# receiver.net
KiCad netlist of a schematic drawn in EAGLE
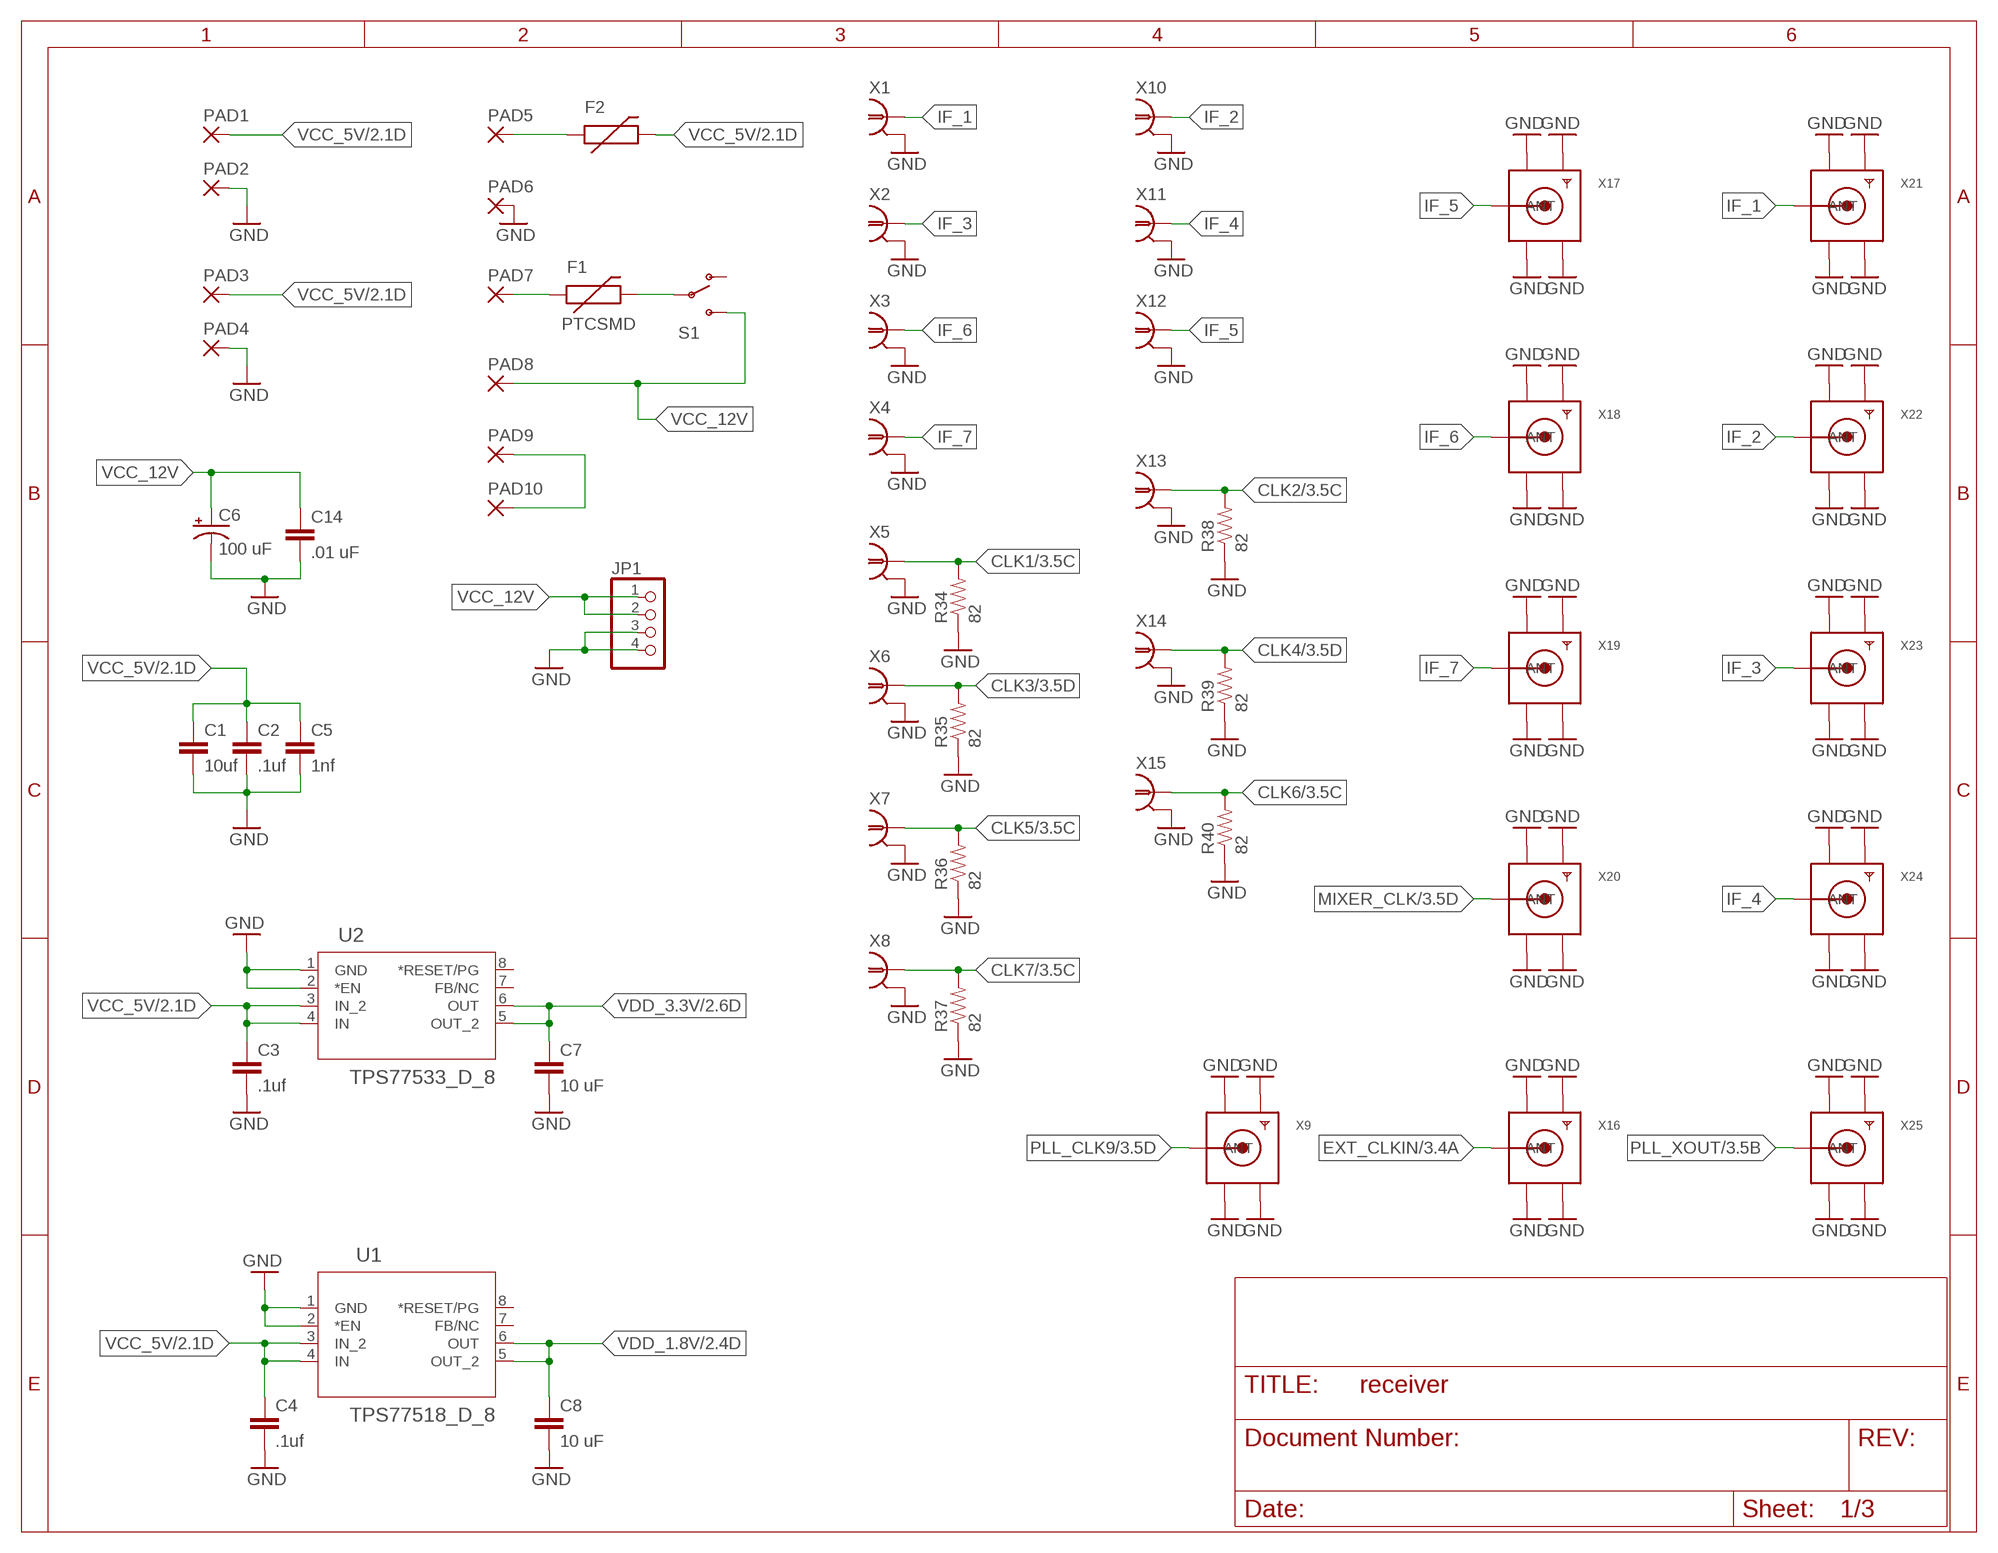
[diagram p0: schematic, sheet 1]
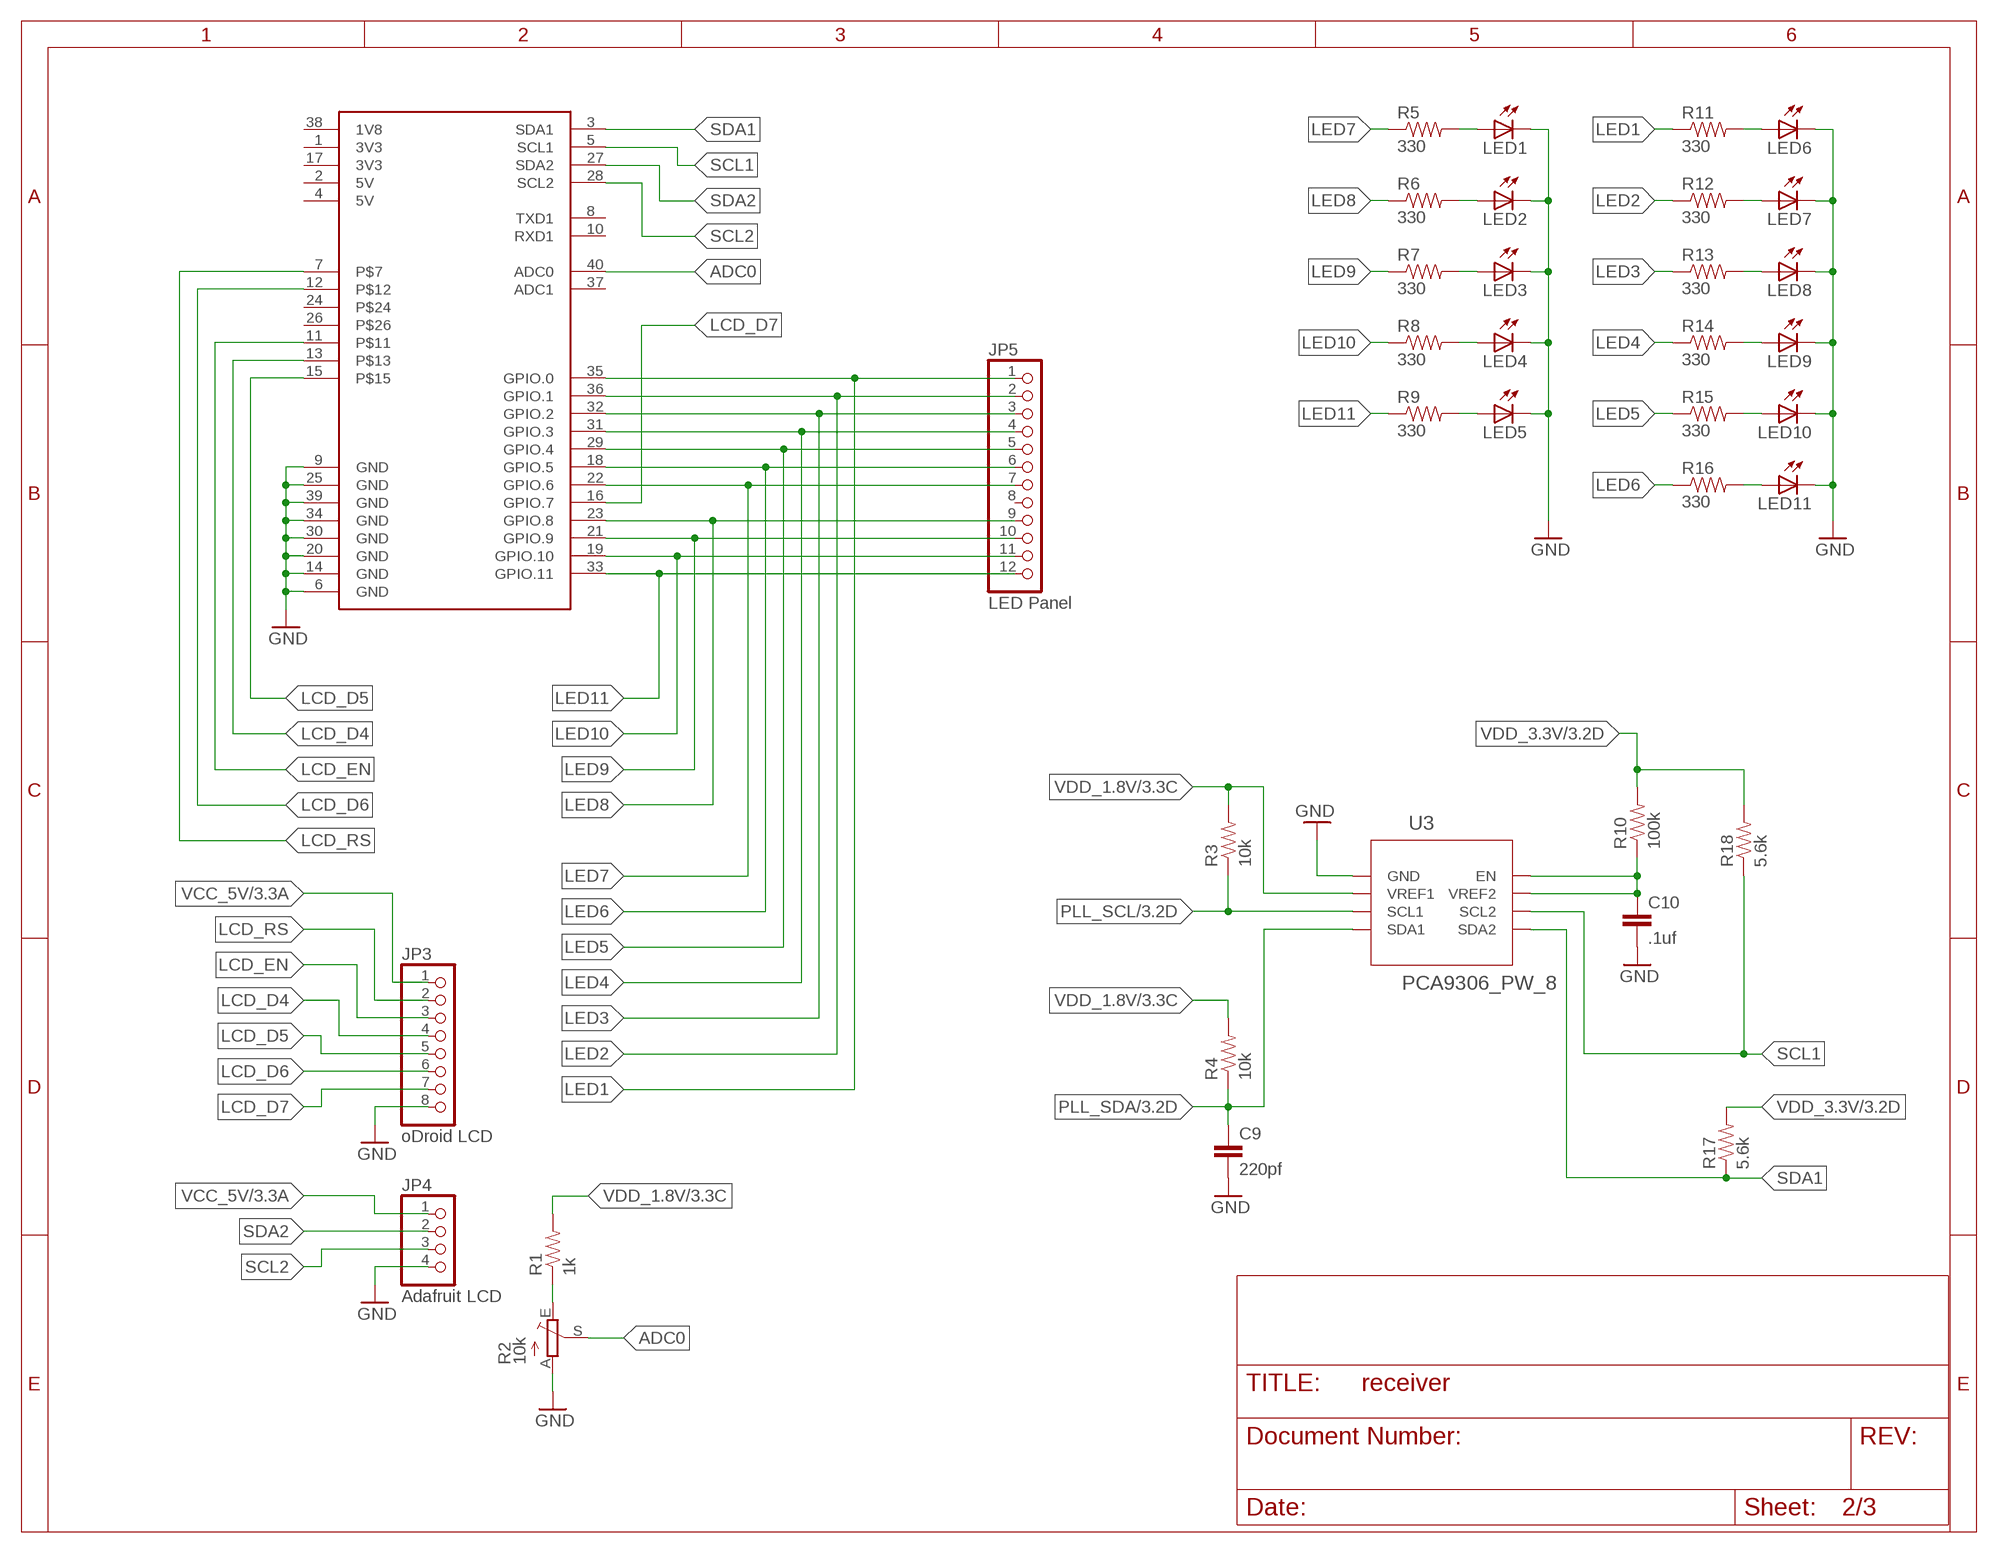
[diagram p1: schematic, sheet 2]
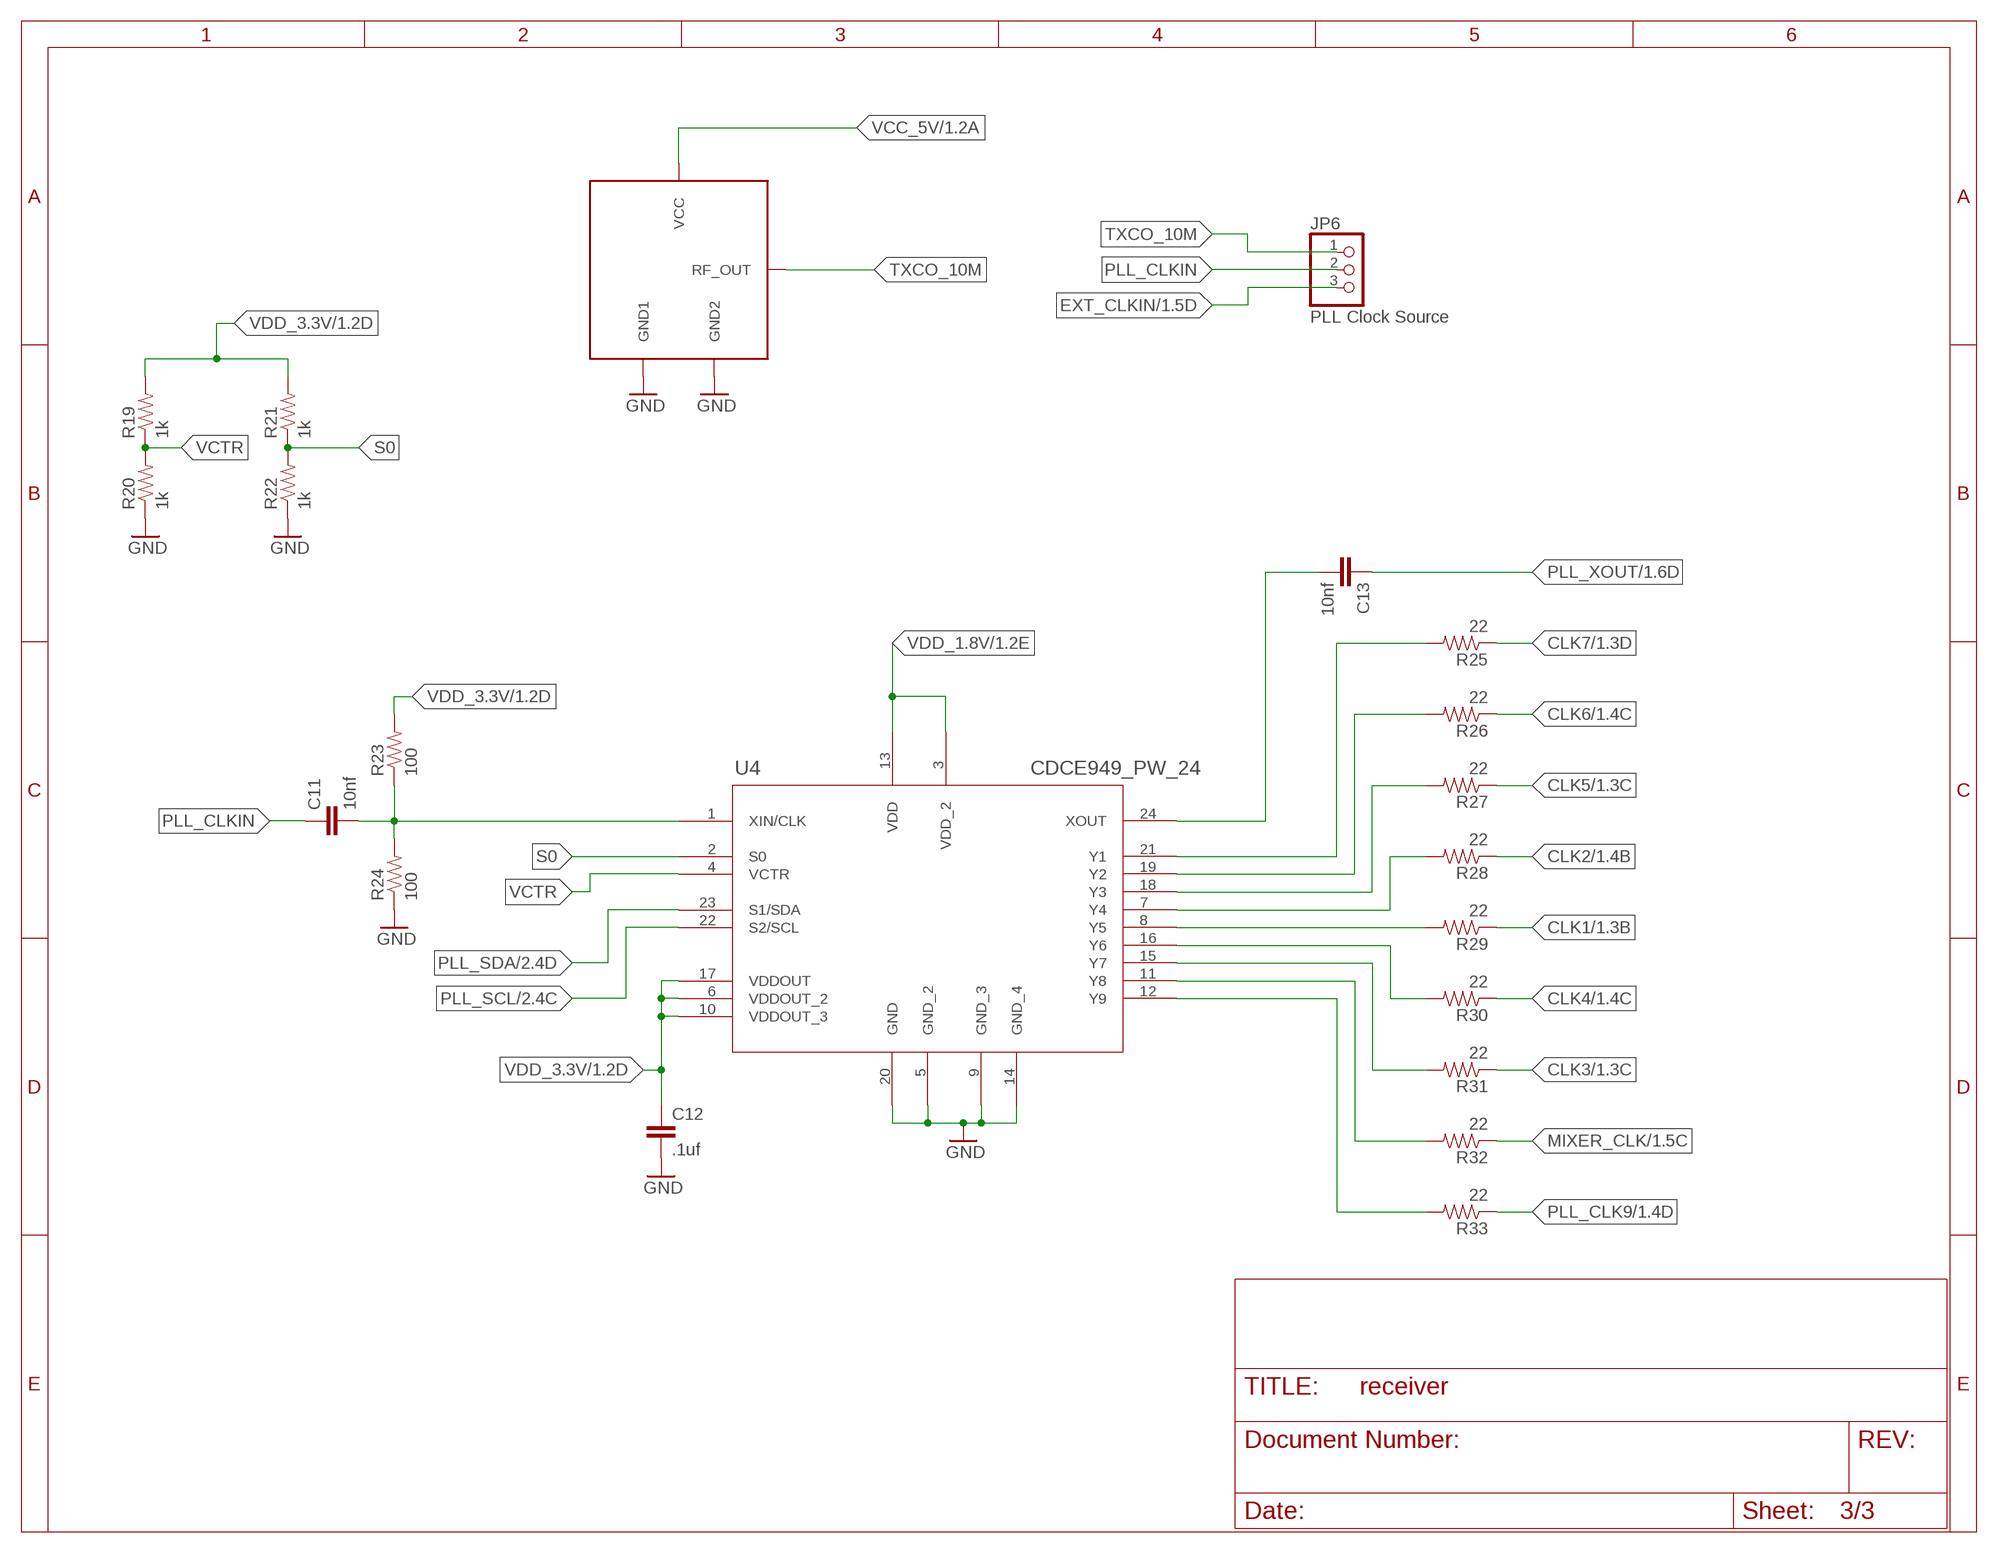
[diagram p2: schematic, sheet 3]

(export (version "E")
  (design (tool "Eeschema 10.0.6"))
  (components
    (comp (ref "C1")
      (value "10uf")
      (footprint "eagle-import:1206")
      (libsource (lib "eagle-import") (part "CAP1206"))
    )
    (comp (ref "C2")
      (value ".1uf")
      (footprint "eagle-import:0805")
      (libsource (lib "eagle-import") (part "CAP0805"))
    )
    (comp (ref "C3")
      (value ".1uf")
      (footprint "eagle-import:0805")
      (libsource (lib "eagle-import") (part "CAP0805"))
    )
    (comp (ref "C4")
      (value ".1uf")
      (footprint "eagle-import:0805")
      (libsource (lib "eagle-import") (part "CAP0805"))
    )
    (comp (ref "C5")
      (value "1nf")
      (footprint "eagle-import:0805")
      (libsource (lib "eagle-import") (part "CAP0805"))
    )
    (comp (ref "C6")
      (value "100 uF")
      (footprint "eagle-import:CPOL-RADIAL-1000UF-25V")
      (libsource (lib "eagle-import") (part "CAP_POLPTH4"))
    )
    (comp (ref "C7")
      (value "10 uF")
      (footprint "eagle-import:1206")
      (libsource (lib "eagle-import") (part "CAP1206"))
    )
    (comp (ref "C8")
      (value "10 uF")
      (footprint "eagle-import:1206")
      (libsource (lib "eagle-import") (part "CAP1206"))
    )
    (comp (ref "C14")
      (value ".01 uF")
      (footprint "eagle-import:0805")
      (libsource (lib "eagle-import") (part "CAP0805"))
    )
    (comp (ref "F1")
      (value "PTCSMD")
      (footprint "eagle-import:PTC-1206")
      (libsource (lib "eagle-import") (part "PTCSMD"))
    )
    (comp (ref "F2")
      (value "PTCSMD")
      (footprint "eagle-import:PTC-1206")
      (libsource (lib "eagle-import") (part "PTCSMD"))
    )
    (comp (ref "JP1")
      (value "PINHD-1X4")
      (footprint "eagle-import:1X04")
      (libsource (lib "eagle-import") (part "PINHD-1X4"))
    )
    (comp (ref "PAD1")
      (value "WIREPAD2,54/0,9")
      (footprint "eagle-import:2,54_0,9")
      (libsource (lib "eagle-import") (part "WIREPAD2,54/0,9"))
    )
    (comp (ref "PAD2")
      (value "WIREPAD2,54/0,9")
      (footprint "eagle-import:2,54_0,9")
      (libsource (lib "eagle-import") (part "WIREPAD2,54/0,9"))
    )
    (comp (ref "PAD3")
      (value "WIREPAD2,54/0,9")
      (footprint "eagle-import:2,54_0,9")
      (libsource (lib "eagle-import") (part "WIREPAD2,54/0,9"))
    )
    (comp (ref "PAD4")
      (value "WIREPAD2,54/0,9")
      (footprint "eagle-import:2,54_0,9")
      (libsource (lib "eagle-import") (part "WIREPAD2,54/0,9"))
    )
    (comp (ref "PAD5")
      (value "WIREPAD2,54/0,9")
      (footprint "eagle-import:2,54_0,9")
      (libsource (lib "eagle-import") (part "WIREPAD2,54/0,9"))
    )
    (comp (ref "PAD6")
      (value "WIREPAD2,54/0,9")
      (footprint "eagle-import:2,54_0,9")
      (libsource (lib "eagle-import") (part "WIREPAD2,54/0,9"))
    )
    (comp (ref "PAD7")
      (value "WIREPAD2,54/0,9")
      (footprint "eagle-import:2,54_0,9")
      (libsource (lib "eagle-import") (part "WIREPAD2,54/0,9"))
    )
    (comp (ref "PAD8")
      (value "WIREPAD2,54/0,9")
      (footprint "eagle-import:2,54_0,9")
      (libsource (lib "eagle-import") (part "WIREPAD2,54/0,9"))
    )
    (comp (ref "PAD9")
      (value "WIREPAD2,54/0,9")
      (footprint "eagle-import:2,54_0,9")
      (libsource (lib "eagle-import") (part "WIREPAD2,54/0,9"))
    )
    (comp (ref "PAD10")
      (value "WIREPAD2,54/0,9")
      (footprint "eagle-import:2,54_0,9")
      (libsource (lib "eagle-import") (part "WIREPAD2,54/0,9"))
    )
    (comp (ref "R34")
      (value "82")
      (footprint "eagle-import:0805")
      (libsource (lib "eagle-import") (part "RESISTOR0805-RES"))
    )
    (comp (ref "R35")
      (value "82")
      (footprint "eagle-import:0805")
      (libsource (lib "eagle-import") (part "RESISTOR0805-RES"))
    )
    (comp (ref "R36")
      (value "82")
      (footprint "eagle-import:0805")
      (libsource (lib "eagle-import") (part "RESISTOR0805-RES"))
    )
    (comp (ref "R37")
      (value "82")
      (footprint "eagle-import:0805")
      (libsource (lib "eagle-import") (part "RESISTOR0805-RES"))
    )
    (comp (ref "R38")
      (value "82")
      (footprint "eagle-import:0805")
      (libsource (lib "eagle-import") (part "RESISTOR0805-RES"))
    )
    (comp (ref "R39")
      (value "82")
      (footprint "eagle-import:0805")
      (libsource (lib "eagle-import") (part "RESISTOR0805-RES"))
    )
    (comp (ref "R40")
      (value "82")
      (footprint "eagle-import:0805")
      (libsource (lib "eagle-import") (part "RESISTOR0805-RES"))
    )
    (comp (ref "S1")
      (value "SWITCH-SPDTPTH")
      (footprint "eagle-import:SWITCH-SPDT")
      (libsource (lib "eagle-import") (part "SWITCH-SPDTPTH"))
    )
    (comp (ref "U1")
      (value "TPS77518_D_8")
      (footprint "eagle-import:D8")
      (fields
        (field (name "GENERIC_PART_NUMBER") "TPS77518")
        (field (name "MANUFACTURER") "Texas Instruments")
        (field (name "MANUFACTURER_PART_NUMBER") "tps77518_d_8")
      )
      (libsource (lib "eagle-import") (part "TPS77518_D_8"))
    )
    (comp (ref "U2")
      (value "TPS77533_D_8")
      (footprint "eagle-import:D8")
      (fields
        (field (name "GENERIC_PART_NUMBER") "TPS77533")
        (field (name "MANUFACTURER") "Texas Instruments")
        (field (name "MANUFACTURER_PART_NUMBER") "tps77533_d_8")
      )
      (libsource (lib "eagle-import") (part "TPS77533_D_8"))
    )
    (comp (ref "X1")
      (value "LTI-SASF54GT")
      (footprint "eagle-import:LTI-SASF54GT")
      (libsource (lib "eagle-import") (part "LTI-SASF54GT"))
    )
    (comp (ref "X2")
      (value "LTI-SASF54GT")
      (footprint "eagle-import:LTI-SASF54GT")
      (libsource (lib "eagle-import") (part "LTI-SASF54GT"))
    )
    (comp (ref "X3")
      (value "LTI-SASF54GT")
      (footprint "eagle-import:LTI-SASF54GT")
      (libsource (lib "eagle-import") (part "LTI-SASF54GT"))
    )
    (comp (ref "X4")
      (value "LTI-SASF54GT")
      (footprint "eagle-import:LTI-SASF54GT")
      (libsource (lib "eagle-import") (part "LTI-SASF54GT"))
    )
    (comp (ref "X5")
      (value "LTI-SASF54GT")
      (footprint "eagle-import:LTI-SASF54GT")
      (libsource (lib "eagle-import") (part "LTI-SASF54GT"))
    )
    (comp (ref "X6")
      (value "LTI-SASF54GT")
      (footprint "eagle-import:LTI-SASF54GT")
      (libsource (lib "eagle-import") (part "LTI-SASF54GT"))
    )
    (comp (ref "X7")
      (value "LTI-SASF54GT")
      (footprint "eagle-import:LTI-SASF54GT")
      (libsource (lib "eagle-import") (part "LTI-SASF54GT"))
    )
    (comp (ref "X8")
      (value "LTI-SASF54GT")
      (footprint "eagle-import:LTI-SASF54GT")
      (libsource (lib "eagle-import") (part "LTI-SASF54GT"))
    )
    (comp (ref "X9")
      (value "SMACONNECTOR_EDGE")
      (footprint "eagle-import:SMA_EDGELAUNCH")
      (libsource (lib "eagle-import") (part "SMACONNECTOR_EDGE"))
    )
    (comp (ref "X10")
      (value "LTI-SASF54GT")
      (footprint "eagle-import:LTI-SASF54GT")
      (libsource (lib "eagle-import") (part "LTI-SASF54GT"))
    )
    (comp (ref "X11")
      (value "LTI-SASF54GT")
      (footprint "eagle-import:LTI-SASF54GT")
      (libsource (lib "eagle-import") (part "LTI-SASF54GT"))
    )
    (comp (ref "X12")
      (value "LTI-SASF54GT")
      (footprint "eagle-import:LTI-SASF54GT")
      (libsource (lib "eagle-import") (part "LTI-SASF54GT"))
    )
    (comp (ref "X13")
      (value "LTI-SASF54GT")
      (footprint "eagle-import:LTI-SASF54GT")
      (libsource (lib "eagle-import") (part "LTI-SASF54GT"))
    )
    (comp (ref "X14")
      (value "LTI-SASF54GT")
      (footprint "eagle-import:LTI-SASF54GT")
      (libsource (lib "eagle-import") (part "LTI-SASF54GT"))
    )
    (comp (ref "X15")
      (value "LTI-SASF54GT")
      (footprint "eagle-import:LTI-SASF54GT")
      (libsource (lib "eagle-import") (part "LTI-SASF54GT"))
    )
    (comp (ref "X16")
      (value "SMACONNECTOR_EDGE")
      (footprint "eagle-import:SMA_EDGELAUNCH")
      (libsource (lib "eagle-import") (part "SMACONNECTOR_EDGE"))
    )
    (comp (ref "X17")
      (value "SMACONNECTOR_EDGE")
      (footprint "eagle-import:SMA_EDGELAUNCH")
      (libsource (lib "eagle-import") (part "SMACONNECTOR_EDGE"))
    )
    (comp (ref "X18")
      (value "SMACONNECTOR_EDGE")
      (footprint "eagle-import:SMA_EDGELAUNCH")
      (libsource (lib "eagle-import") (part "SMACONNECTOR_EDGE"))
    )
    (comp (ref "X19")
      (value "SMACONNECTOR_EDGE")
      (footprint "eagle-import:SMA_EDGELAUNCH")
      (libsource (lib "eagle-import") (part "SMACONNECTOR_EDGE"))
    )
    (comp (ref "X20")
      (value "SMACONNECTOR_EDGE")
      (footprint "eagle-import:SMA_EDGELAUNCH")
      (libsource (lib "eagle-import") (part "SMACONNECTOR_EDGE"))
    )
    (comp (ref "X21")
      (value "SMACONNECTOR_EDGE")
      (footprint "eagle-import:SMA_EDGELAUNCH")
      (libsource (lib "eagle-import") (part "SMACONNECTOR_EDGE"))
    )
    (comp (ref "X22")
      (value "SMACONNECTOR_EDGE")
      (footprint "eagle-import:SMA_EDGELAUNCH")
      (libsource (lib "eagle-import") (part "SMACONNECTOR_EDGE"))
    )
    (comp (ref "X23")
      (value "SMACONNECTOR_EDGE")
      (footprint "eagle-import:SMA_EDGELAUNCH")
      (libsource (lib "eagle-import") (part "SMACONNECTOR_EDGE"))
    )
    (comp (ref "X24")
      (value "SMACONNECTOR_EDGE")
      (footprint "eagle-import:SMA_EDGELAUNCH")
      (libsource (lib "eagle-import") (part "SMACONNECTOR_EDGE"))
    )
    (comp (ref "X25")
      (value "SMACONNECTOR_EDGE")
      (footprint "eagle-import:SMA_EDGELAUNCH")
      (libsource (lib "eagle-import") (part "SMACONNECTOR_EDGE"))
    )
    (comp (ref "C9")
      (value "220pf")
      (footprint "eagle-import:0805")
      (libsource (lib "eagle-import") (part "CAP0805"))
    )
    (comp (ref "C10")
      (value ".1uf")
      (footprint "eagle-import:0805")
      (libsource (lib "eagle-import") (part "CAP0805"))
    )
    (comp (ref "JP2")
      (value "C1_GPIO")
      (footprint "eagle-import:2X20-BIG")
      (libsource (lib "eagle-import") (part "C1_GPIO"))
    )
    (comp (ref "JP3")
      (value "oDroid LCD")
      (footprint "eagle-import:1X08")
      (libsource (lib "eagle-import") (part "PINHD-1X8"))
    )
    (comp (ref "JP4")
      (value "Adafruit LCD")
      (footprint "eagle-import:1X04")
      (libsource (lib "eagle-import") (part "PINHD-1X4"))
    )
    (comp (ref "JP5")
      (value "LED Panel")
      (footprint "eagle-import:1X12")
      (libsource (lib "eagle-import") (part "PINHD-1X12"))
    )
    (comp (ref "LED1")
      (value "LEDCHIPLED_1206")
      (footprint "eagle-import:CHIPLED_1206")
      (libsource (lib "eagle-import") (part "LEDCHIPLED_1206"))
    )
    (comp (ref "LED2")
      (value "LEDCHIPLED_1206")
      (footprint "eagle-import:CHIPLED_1206")
      (libsource (lib "eagle-import") (part "LEDCHIPLED_1206"))
    )
    (comp (ref "LED3")
      (value "LEDCHIPLED_1206")
      (footprint "eagle-import:CHIPLED_1206")
      (libsource (lib "eagle-import") (part "LEDCHIPLED_1206"))
    )
    (comp (ref "LED4")
      (value "LEDCHIPLED_1206")
      (footprint "eagle-import:CHIPLED_1206")
      (libsource (lib "eagle-import") (part "LEDCHIPLED_1206"))
    )
    (comp (ref "LED5")
      (value "LEDCHIPLED_1206")
      (footprint "eagle-import:CHIPLED_1206")
      (libsource (lib "eagle-import") (part "LEDCHIPLED_1206"))
    )
    (comp (ref "LED6")
      (value "LEDCHIPLED_1206")
      (footprint "eagle-import:CHIPLED_1206")
      (libsource (lib "eagle-import") (part "LEDCHIPLED_1206"))
    )
    (comp (ref "LED7")
      (value "LEDCHIPLED_1206")
      (footprint "eagle-import:CHIPLED_1206")
      (libsource (lib "eagle-import") (part "LEDCHIPLED_1206"))
    )
    (comp (ref "LED8")
      (value "LEDCHIPLED_1206")
      (footprint "eagle-import:CHIPLED_1206")
      (libsource (lib "eagle-import") (part "LEDCHIPLED_1206"))
    )
    (comp (ref "LED9")
      (value "LEDCHIPLED_1206")
      (footprint "eagle-import:CHIPLED_1206")
      (libsource (lib "eagle-import") (part "LEDCHIPLED_1206"))
    )
    (comp (ref "LED10")
      (value "LEDCHIPLED_1206")
      (footprint "eagle-import:CHIPLED_1206")
      (libsource (lib "eagle-import") (part "LEDCHIPLED_1206"))
    )
    (comp (ref "LED11")
      (value "LEDCHIPLED_1206")
      (footprint "eagle-import:CHIPLED_1206")
      (libsource (lib "eagle-import") (part "LEDCHIPLED_1206"))
    )
    (comp (ref "R1")
      (value "1k")
      (footprint "eagle-import:0805")
      (libsource (lib "eagle-import") (part "RESISTOR0805-RES"))
    )
    (comp (ref "R2")
      (value "10k")
      (footprint "eagle-import:B64Y")
      (libsource (lib "eagle-import") (part "TRIM_EU-B64Y"))
    )
    (comp (ref "R3")
      (value "10k")
      (footprint "eagle-import:0805")
      (libsource (lib "eagle-import") (part "RESISTOR0805-RES"))
    )
    (comp (ref "R4")
      (value "10k")
      (footprint "eagle-import:0805")
      (libsource (lib "eagle-import") (part "RESISTOR0805-RES"))
    )
    (comp (ref "R5")
      (value "330")
      (footprint "eagle-import:0805")
      (libsource (lib "eagle-import") (part "RESISTOR0805-RES"))
    )
    (comp (ref "R6")
      (value "330")
      (footprint "eagle-import:0805")
      (libsource (lib "eagle-import") (part "RESISTOR0805-RES"))
    )
    (comp (ref "R7")
      (value "330")
      (footprint "eagle-import:0805")
      (libsource (lib "eagle-import") (part "RESISTOR0805-RES"))
    )
    (comp (ref "R8")
      (value "330")
      (footprint "eagle-import:0805")
      (libsource (lib "eagle-import") (part "RESISTOR0805-RES"))
    )
    (comp (ref "R9")
      (value "330")
      (footprint "eagle-import:0805")
      (libsource (lib "eagle-import") (part "RESISTOR0805-RES"))
    )
    (comp (ref "R10")
      (value "100k")
      (footprint "eagle-import:0805")
      (libsource (lib "eagle-import") (part "RESISTOR0805-RES"))
    )
    (comp (ref "R11")
      (value "330")
      (footprint "eagle-import:0805")
      (libsource (lib "eagle-import") (part "RESISTOR0805-RES"))
    )
    (comp (ref "R12")
      (value "330")
      (footprint "eagle-import:0805")
      (libsource (lib "eagle-import") (part "RESISTOR0805-RES"))
    )
    (comp (ref "R13")
      (value "330")
      (footprint "eagle-import:0805")
      (libsource (lib "eagle-import") (part "RESISTOR0805-RES"))
    )
    (comp (ref "R14")
      (value "330")
      (footprint "eagle-import:0805")
      (libsource (lib "eagle-import") (part "RESISTOR0805-RES"))
    )
    (comp (ref "R15")
      (value "330")
      (footprint "eagle-import:0805")
      (libsource (lib "eagle-import") (part "RESISTOR0805-RES"))
    )
    (comp (ref "R16")
      (value "330")
      (footprint "eagle-import:0805")
      (libsource (lib "eagle-import") (part "RESISTOR0805-RES"))
    )
    (comp (ref "R17")
      (value "5.6k")
      (footprint "eagle-import:0805")
      (libsource (lib "eagle-import") (part "RESISTOR0805-RES"))
    )
    (comp (ref "R18")
      (value "5.6k")
      (footprint "eagle-import:0805")
      (libsource (lib "eagle-import") (part "RESISTOR0805-RES"))
    )
    (comp (ref "U3")
      (value "PCA9306_PW_8")
      (footprint "eagle-import:PW8")
      (fields
        (field (name "GENERIC_PART_NUMBER") "PCA9306")
        (field (name "MANUFACTURER") "Texas Instruments")
        (field (name "MANUFACTURER_PART_NUMBER") "pca9306_pw_8")
      )
      (libsource (lib "eagle-import") (part "PCA9306_PW_8"))
    )
    (comp (ref "$3_194_$_2015-06-18_19-54-36")
      (value "TXCO 10M")
      (footprint "eagle-import:THRU-HOLE")
      (libsource (lib "eagle-import") (part "TCXO-10MTHRU-HOLE"))
    )
    (comp (ref "C11")
      (value "10nf")
      (footprint "eagle-import:0805")
      (libsource (lib "eagle-import") (part "CAP0805"))
    )
    (comp (ref "C12")
      (value ".1uf")
      (footprint "eagle-import:0805")
      (libsource (lib "eagle-import") (part "CAP0805"))
    )
    (comp (ref "C13")
      (value "10nf")
      (footprint "eagle-import:0805")
      (libsource (lib "eagle-import") (part "CAP0805"))
    )
    (comp (ref "JP6")
      (value "PLL Clock Source")
      (footprint "eagle-import:1X03")
      (libsource (lib "eagle-import") (part "PINHD-1X3"))
    )
    (comp (ref "R19")
      (value "1k")
      (footprint "eagle-import:0805")
      (libsource (lib "eagle-import") (part "RESISTOR0805-RES"))
    )
    (comp (ref "R20")
      (value "1k")
      (footprint "eagle-import:0805")
      (libsource (lib "eagle-import") (part "RESISTOR0805-RES"))
    )
    (comp (ref "R21")
      (value "1k")
      (footprint "eagle-import:0805")
      (libsource (lib "eagle-import") (part "RESISTOR0805-RES"))
    )
    (comp (ref "R22")
      (value "1k")
      (footprint "eagle-import:0805")
      (libsource (lib "eagle-import") (part "RESISTOR0805-RES"))
    )
    (comp (ref "R23")
      (value "100")
      (footprint "eagle-import:0805")
      (libsource (lib "eagle-import") (part "RESISTOR0805-RES"))
    )
    (comp (ref "R24")
      (value "100")
      (footprint "eagle-import:0805")
      (libsource (lib "eagle-import") (part "RESISTOR0805-RES"))
    )
    (comp (ref "R25")
      (value "22")
      (footprint "eagle-import:0805")
      (libsource (lib "eagle-import") (part "RESISTOR0805-RES"))
    )
    (comp (ref "R26")
      (value "22")
      (footprint "eagle-import:0805")
      (libsource (lib "eagle-import") (part "RESISTOR0805-RES"))
    )
    (comp (ref "R27")
      (value "22")
      (footprint "eagle-import:0805")
      (libsource (lib "eagle-import") (part "RESISTOR0805-RES"))
    )
    (comp (ref "R28")
      (value "22")
      (footprint "eagle-import:0805")
      (libsource (lib "eagle-import") (part "RESISTOR0805-RES"))
    )
    (comp (ref "R29")
      (value "22")
      (footprint "eagle-import:0805")
      (libsource (lib "eagle-import") (part "RESISTOR0805-RES"))
    )
    (comp (ref "R30")
      (value "22")
      (footprint "eagle-import:0805")
      (libsource (lib "eagle-import") (part "RESISTOR0805-RES"))
    )
    (comp (ref "R31")
      (value "22")
      (footprint "eagle-import:0805")
      (libsource (lib "eagle-import") (part "RESISTOR0805-RES"))
    )
    (comp (ref "R32")
      (value "22")
      (footprint "eagle-import:0805")
      (libsource (lib "eagle-import") (part "RESISTOR0805-RES"))
    )
    (comp (ref "R33")
      (value "22")
      (footprint "eagle-import:0805")
      (libsource (lib "eagle-import") (part "RESISTOR0805-RES"))
    )
    (comp (ref "U4")
      (value "CDCE949_PW_24")
      (footprint "eagle-import:PW24")
      (fields
        (field (name "GENERIC_PART_NUMBER") "CDCE949")
        (field (name "MANUFACTURER") "Texas Instruments")
      )
      (libsource (lib "eagle-import") (part "CDCE949_PW_24"))
    )
  )
  (nets
    (net (code "1") (name "ADC0") (class "Default")
      (node (ref "JP2") (pin "40") (pinfunction "ADC0_40") (pintype "bidirectional"))
      (node (ref "R2") (pin "S") (pinfunction "S_S") (pintype "passive"))
    )
    (net (code "2") (name "CLK1") (class "Default")
      (node (ref "R29") (pin "1") (pinfunction "1_1") (pintype "passive"))
      (node (ref "R34") (pin "2") (pinfunction "2_2") (pintype "passive"))
      (node (ref "X5") (pin "1") (pinfunction "1_1") (pintype "passive"))
    )
    (net (code "3") (name "CLK2") (class "Default")
      (node (ref "R28") (pin "1") (pinfunction "1_1") (pintype "passive"))
      (node (ref "R38") (pin "2") (pinfunction "2_2") (pintype "passive"))
      (node (ref "X13") (pin "1") (pinfunction "1_1") (pintype "passive"))
    )
    (net (code "4") (name "CLK3") (class "Default")
      (node (ref "R31") (pin "1") (pinfunction "1_1") (pintype "passive"))
      (node (ref "R35") (pin "2") (pinfunction "2_2") (pintype "passive"))
      (node (ref "X6") (pin "1") (pinfunction "1_1") (pintype "passive"))
    )
    (net (code "5") (name "CLK4") (class "Default")
      (node (ref "R30") (pin "1") (pinfunction "1_1") (pintype "passive"))
      (node (ref "R39") (pin "2") (pinfunction "2_2") (pintype "passive"))
      (node (ref "X14") (pin "1") (pinfunction "1_1") (pintype "passive"))
    )
    (net (code "6") (name "CLK5") (class "Default")
      (node (ref "R27") (pin "1") (pinfunction "1_1") (pintype "passive"))
      (node (ref "R36") (pin "2") (pinfunction "2_2") (pintype "passive"))
      (node (ref "X7") (pin "1") (pinfunction "1_1") (pintype "passive"))
    )
    (net (code "7") (name "CLK6") (class "Default")
      (node (ref "R26") (pin "1") (pinfunction "1_1") (pintype "passive"))
      (node (ref "R40") (pin "2") (pinfunction "2_2") (pintype "passive"))
      (node (ref "X15") (pin "1") (pinfunction "1_1") (pintype "passive"))
    )
    (net (code "8") (name "CLK7") (class "Default")
      (node (ref "R25") (pin "1") (pinfunction "1_1") (pintype "passive"))
      (node (ref "R37") (pin "2") (pinfunction "2_2") (pintype "passive"))
      (node (ref "X8") (pin "1") (pinfunction "1_1") (pintype "passive"))
    )
    (net (code "9") (name "EXT_CLKIN") (class "Default")
      (node (ref "JP6") (pin "3") (pinfunction "3_3") (pintype "passive"))
      (node (ref "X16") (pin "P") (pinfunction "ANT_P") (pintype "bidirectional"))
    )
    (net (code "10") (name "GND") (class "Default")
      (node (ref "$3_194_$_2015-06-18_19-54-36") (pin "GND1") (pinfunction "GND1_GND1") (pintype "power_in"))
      (node (ref "$3_194_$_2015-06-18_19-54-36") (pin "GND2") (pinfunction "GND2_GND2") (pintype "power_in"))
      (node (ref "C1") (pin "2") (pinfunction "2_2") (pintype "passive"))
      (node (ref "C10") (pin "2") (pinfunction "2_2") (pintype "passive"))
      (node (ref "C12") (pin "2") (pinfunction "2_2") (pintype "passive"))
      (node (ref "C14") (pin "2") (pinfunction "2_2") (pintype "passive"))
      (node (ref "C2") (pin "2") (pinfunction "2_2") (pintype "passive"))
      (node (ref "C3") (pin "2") (pinfunction "2_2") (pintype "passive"))
      (node (ref "C4") (pin "2") (pinfunction "2_2") (pintype "passive"))
      (node (ref "C5") (pin "2") (pinfunction "2_2") (pintype "passive"))
      (node (ref "C6") (pin "-") (pinfunction "-_-") (pintype "passive"))
      (node (ref "C7") (pin "2") (pinfunction "2_2") (pintype "passive"))
      (node (ref "C8") (pin "2") (pinfunction "2_2") (pintype "passive"))
      (node (ref "C9") (pin "2") (pinfunction "2_2") (pintype "passive"))
      (node (ref "JP1") (pin "3") (pinfunction "3_3") (pintype "passive"))
      (node (ref "JP1") (pin "4") (pinfunction "4_4") (pintype "passive"))
      (node (ref "JP2") (pin "14") (pinfunction "GND_14") (pintype "power_in"))
      (node (ref "JP2") (pin "20") (pinfunction "GND_20") (pintype "power_in"))
      (node (ref "JP2") (pin "25") (pinfunction "GND_25") (pintype "power_in"))
      (node (ref "JP2") (pin "30") (pinfunction "GND_30") (pintype "power_in"))
      (node (ref "JP2") (pin "34") (pinfunction "GND_34") (pintype "power_in"))
      (node (ref "JP2") (pin "39") (pinfunction "GND_39") (pintype "power_in"))
      (node (ref "JP2") (pin "6") (pinfunction "GND_6") (pintype "power_in"))
      (node (ref "JP2") (pin "9") (pinfunction "GND_9") (pintype "power_in"))
      (node (ref "JP3") (pin "8") (pinfunction "8_8") (pintype "passive"))
      (node (ref "JP4") (pin "4") (pinfunction "4_4") (pintype "passive"))
      (node (ref "LED1") (pin "C") (pinfunction "C_C") (pintype "passive"))
      (node (ref "LED10") (pin "C") (pinfunction "C_C") (pintype "passive"))
      (node (ref "LED11") (pin "C") (pinfunction "C_C") (pintype "passive"))
      (node (ref "LED2") (pin "C") (pinfunction "C_C") (pintype "passive"))
      (node (ref "LED3") (pin "C") (pinfunction "C_C") (pintype "passive"))
      (node (ref "LED4") (pin "C") (pinfunction "C_C") (pintype "passive"))
      (node (ref "LED5") (pin "C") (pinfunction "C_C") (pintype "passive"))
      (node (ref "LED6") (pin "C") (pinfunction "C_C") (pintype "passive"))
      (node (ref "LED7") (pin "C") (pinfunction "C_C") (pintype "passive"))
      (node (ref "LED8") (pin "C") (pinfunction "C_C") (pintype "passive"))
      (node (ref "LED9") (pin "C") (pinfunction "C_C") (pintype "passive"))
      (node (ref "PAD2") (pin "1") (pinfunction "P_1") (pintype "passive"))
      (node (ref "PAD4") (pin "1") (pinfunction "P_1") (pintype "passive"))
      (node (ref "PAD6") (pin "1") (pinfunction "P_1") (pintype "passive"))
      (node (ref "R2") (pin "A") (pinfunction "A_A") (pintype "passive"))
      (node (ref "R20") (pin "1") (pinfunction "1_1") (pintype "passive"))
      (node (ref "R22") (pin "1") (pinfunction "1_1") (pintype "passive"))
      (node (ref "R24") (pin "1") (pinfunction "1_1") (pintype "passive"))
      (node (ref "R34") (pin "1") (pinfunction "1_1") (pintype "passive"))
      (node (ref "R35") (pin "1") (pinfunction "1_1") (pintype "passive"))
      (node (ref "R36") (pin "1") (pinfunction "1_1") (pintype "passive"))
      (node (ref "R37") (pin "1") (pinfunction "1_1") (pintype "passive"))
      (node (ref "R38") (pin "1") (pinfunction "1_1") (pintype "passive"))
      (node (ref "R39") (pin "1") (pinfunction "1_1") (pintype "passive"))
      (node (ref "R40") (pin "1") (pinfunction "1_1") (pintype "passive"))
      (node (ref "U1") (pin "1") (pinfunction "GND_1") (pintype "power_in"))
      (node (ref "U1") (pin "2") (pinfunction "*EN_2") (pintype "input"))
      (node (ref "U2") (pin "1") (pinfunction "GND_1") (pintype "power_in"))
      (node (ref "U2") (pin "2") (pinfunction "*EN_2") (pintype "input"))
      (node (ref "U3") (pin "1") (pinfunction "GND_1") (pintype "power_in"))
      (node (ref "U4") (pin "14") (pinfunction "GND_4_14") (pintype "power_in"))
      (node (ref "U4") (pin "20") (pinfunction "GND_20") (pintype "power_in"))
      (node (ref "U4") (pin "5") (pinfunction "GND_2_5") (pintype "power_in"))
      (node (ref "U4") (pin "9") (pinfunction "GND_3_9") (pintype "power_in"))
      (node (ref "X1") (pin "2") (pinfunction "2_2") (pintype "passive"))
      (node (ref "X1") (pin "3") (pinfunction "2_3") (pintype "passive"))
      (node (ref "X1") (pin "4") (pinfunction "2_4") (pintype "passive"))
      (node (ref "X1") (pin "5") (pinfunction "2_5") (pintype "passive"))
      (node (ref "X10") (pin "2") (pinfunction "2_2") (pintype "passive"))
      (node (ref "X10") (pin "3") (pinfunction "2_3") (pintype "passive"))
      (node (ref "X10") (pin "4") (pinfunction "2_4") (pintype "passive"))
      (node (ref "X10") (pin "5") (pinfunction "2_5") (pintype "passive"))
      (node (ref "X11") (pin "2") (pinfunction "2_2") (pintype "passive"))
      (node (ref "X11") (pin "3") (pinfunction "2_3") (pintype "passive"))
      (node (ref "X11") (pin "4") (pinfunction "2_4") (pintype "passive"))
      (node (ref "X11") (pin "5") (pinfunction "2_5") (pintype "passive"))
      (node (ref "X12") (pin "2") (pinfunction "2_2") (pintype "passive"))
      (node (ref "X12") (pin "3") (pinfunction "2_3") (pintype "passive"))
      (node (ref "X12") (pin "4") (pinfunction "2_4") (pintype "passive"))
      (node (ref "X12") (pin "5") (pinfunction "2_5") (pintype "passive"))
      (node (ref "X13") (pin "2") (pinfunction "2_2") (pintype "passive"))
      (node (ref "X13") (pin "3") (pinfunction "2_3") (pintype "passive"))
      (node (ref "X13") (pin "4") (pinfunction "2_4") (pintype "passive"))
      (node (ref "X13") (pin "5") (pinfunction "2_5") (pintype "passive"))
      (node (ref "X14") (pin "2") (pinfunction "2_2") (pintype "passive"))
      (node (ref "X14") (pin "3") (pinfunction "2_3") (pintype "passive"))
      (node (ref "X14") (pin "4") (pinfunction "2_4") (pintype "passive"))
      (node (ref "X14") (pin "5") (pinfunction "2_5") (pintype "passive"))
      (node (ref "X15") (pin "2") (pinfunction "2_2") (pintype "passive"))
      (node (ref "X15") (pin "3") (pinfunction "2_3") (pintype "passive"))
      (node (ref "X15") (pin "4") (pinfunction "2_4") (pintype "passive"))
      (node (ref "X15") (pin "5") (pinfunction "2_5") (pintype "passive"))
      (node (ref "X16") (pin "GND@1") (pinfunction "GND4_GND@1") (pintype "power_in"))
      (node (ref "X16") (pin "GND@2") (pinfunction "GND3_GND@2") (pintype "power_in"))
      (node (ref "X16") (pin "GND@3") (pinfunction "GND2_GND@3") (pintype "power_in"))
      (node (ref "X16") (pin "GND@4") (pinfunction "GND1_GND@4") (pintype "power_in"))
      (node (ref "X17") (pin "GND@1") (pinfunction "GND4_GND@1") (pintype "power_in"))
      (node (ref "X17") (pin "GND@2") (pinfunction "GND3_GND@2") (pintype "power_in"))
      (node (ref "X17") (pin "GND@3") (pinfunction "GND2_GND@3") (pintype "power_in"))
      (node (ref "X17") (pin "GND@4") (pinfunction "GND1_GND@4") (pintype "power_in"))
      (node (ref "X18") (pin "GND@1") (pinfunction "GND4_GND@1") (pintype "power_in"))
      (node (ref "X18") (pin "GND@2") (pinfunction "GND3_GND@2") (pintype "power_in"))
      (node (ref "X18") (pin "GND@3") (pinfunction "GND2_GND@3") (pintype "power_in"))
      (node (ref "X18") (pin "GND@4") (pinfunction "GND1_GND@4") (pintype "power_in"))
      (node (ref "X19") (pin "GND@1") (pinfunction "GND4_GND@1") (pintype "power_in"))
      (node (ref "X19") (pin "GND@2") (pinfunction "GND3_GND@2") (pintype "power_in"))
      (node (ref "X19") (pin "GND@3") (pinfunction "GND2_GND@3") (pintype "power_in"))
      (node (ref "X19") (pin "GND@4") (pinfunction "GND1_GND@4") (pintype "power_in"))
      (node (ref "X2") (pin "2") (pinfunction "2_2") (pintype "passive"))
      (node (ref "X2") (pin "3") (pinfunction "2_3") (pintype "passive"))
      (node (ref "X2") (pin "4") (pinfunction "2_4") (pintype "passive"))
      (node (ref "X2") (pin "5") (pinfunction "2_5") (pintype "passive"))
      (node (ref "X20") (pin "GND@1") (pinfunction "GND4_GND@1") (pintype "power_in"))
      (node (ref "X20") (pin "GND@2") (pinfunction "GND3_GND@2") (pintype "power_in"))
      (node (ref "X20") (pin "GND@3") (pinfunction "GND2_GND@3") (pintype "power_in"))
      (node (ref "X20") (pin "GND@4") (pinfunction "GND1_GND@4") (pintype "power_in"))
      (node (ref "X21") (pin "GND@1") (pinfunction "GND4_GND@1") (pintype "power_in"))
      (node (ref "X21") (pin "GND@2") (pinfunction "GND3_GND@2") (pintype "power_in"))
      (node (ref "X21") (pin "GND@3") (pinfunction "GND2_GND@3") (pintype "power_in"))
      (node (ref "X21") (pin "GND@4") (pinfunction "GND1_GND@4") (pintype "power_in"))
      (node (ref "X22") (pin "GND@1") (pinfunction "GND4_GND@1") (pintype "power_in"))
      (node (ref "X22") (pin "GND@2") (pinfunction "GND3_GND@2") (pintype "power_in"))
      (node (ref "X22") (pin "GND@3") (pinfunction "GND2_GND@3") (pintype "power_in"))
      (node (ref "X22") (pin "GND@4") (pinfunction "GND1_GND@4") (pintype "power_in"))
      (node (ref "X23") (pin "GND@1") (pinfunction "GND4_GND@1") (pintype "power_in"))
      (node (ref "X23") (pin "GND@2") (pinfunction "GND3_GND@2") (pintype "power_in"))
      (node (ref "X23") (pin "GND@3") (pinfunction "GND2_GND@3") (pintype "power_in"))
      (node (ref "X23") (pin "GND@4") (pinfunction "GND1_GND@4") (pintype "power_in"))
      (node (ref "X24") (pin "GND@1") (pinfunction "GND4_GND@1") (pintype "power_in"))
      (node (ref "X24") (pin "GND@2") (pinfunction "GND3_GND@2") (pintype "power_in"))
      (node (ref "X24") (pin "GND@3") (pinfunction "GND2_GND@3") (pintype "power_in"))
      (node (ref "X24") (pin "GND@4") (pinfunction "GND1_GND@4") (pintype "power_in"))
      (node (ref "X25") (pin "GND@1") (pinfunction "GND4_GND@1") (pintype "power_in"))
      (node (ref "X25") (pin "GND@2") (pinfunction "GND3_GND@2") (pintype "power_in"))
      (node (ref "X25") (pin "GND@3") (pinfunction "GND2_GND@3") (pintype "power_in"))
      (node (ref "X25") (pin "GND@4") (pinfunction "GND1_GND@4") (pintype "power_in"))
      (node (ref "X3") (pin "2") (pinfunction "2_2") (pintype "passive"))
      (node (ref "X3") (pin "3") (pinfunction "2_3") (pintype "passive"))
      (node (ref "X3") (pin "4") (pinfunction "2_4") (pintype "passive"))
      (node (ref "X3") (pin "5") (pinfunction "2_5") (pintype "passive"))
      (node (ref "X4") (pin "2") (pinfunction "2_2") (pintype "passive"))
      (node (ref "X4") (pin "3") (pinfunction "2_3") (pintype "passive"))
      (node (ref "X4") (pin "4") (pinfunction "2_4") (pintype "passive"))
      (node (ref "X4") (pin "5") (pinfunction "2_5") (pintype "passive"))
      (node (ref "X5") (pin "2") (pinfunction "2_2") (pintype "passive"))
      (node (ref "X5") (pin "3") (pinfunction "2_3") (pintype "passive"))
      (node (ref "X5") (pin "4") (pinfunction "2_4") (pintype "passive"))
      (node (ref "X5") (pin "5") (pinfunction "2_5") (pintype "passive"))
      (node (ref "X6") (pin "2") (pinfunction "2_2") (pintype "passive"))
      (node (ref "X6") (pin "3") (pinfunction "2_3") (pintype "passive"))
      (node (ref "X6") (pin "4") (pinfunction "2_4") (pintype "passive"))
      (node (ref "X6") (pin "5") (pinfunction "2_5") (pintype "passive"))
      (node (ref "X7") (pin "2") (pinfunction "2_2") (pintype "passive"))
      (node (ref "X7") (pin "3") (pinfunction "2_3") (pintype "passive"))
      (node (ref "X7") (pin "4") (pinfunction "2_4") (pintype "passive"))
      (node (ref "X7") (pin "5") (pinfunction "2_5") (pintype "passive"))
      (node (ref "X8") (pin "2") (pinfunction "2_2") (pintype "passive"))
      (node (ref "X8") (pin "3") (pinfunction "2_3") (pintype "passive"))
      (node (ref "X8") (pin "4") (pinfunction "2_4") (pintype "passive"))
      (node (ref "X8") (pin "5") (pinfunction "2_5") (pintype "passive"))
      (node (ref "X9") (pin "GND@1") (pinfunction "GND4_GND@1") (pintype "power_in"))
      (node (ref "X9") (pin "GND@2") (pinfunction "GND3_GND@2") (pintype "power_in"))
      (node (ref "X9") (pin "GND@3") (pinfunction "GND2_GND@3") (pintype "power_in"))
      (node (ref "X9") (pin "GND@4") (pinfunction "GND1_GND@4") (pintype "power_in"))
    )
    (net (code "11") (name "IF_1") (class "Default")
      (node (ref "X1") (pin "1") (pinfunction "1_1") (pintype "passive"))
      (node (ref "X21") (pin "P") (pinfunction "ANT_P") (pintype "bidirectional"))
    )
    (net (code "12") (name "IF_2") (class "Default")
      (node (ref "X10") (pin "1") (pinfunction "1_1") (pintype "passive"))
      (node (ref "X22") (pin "P") (pinfunction "ANT_P") (pintype "bidirectional"))
    )
    (net (code "13") (name "IF_3") (class "Default")
      (node (ref "X2") (pin "1") (pinfunction "1_1") (pintype "passive"))
      (node (ref "X23") (pin "P") (pinfunction "ANT_P") (pintype "bidirectional"))
    )
    (net (code "14") (name "IF_4") (class "Default")
      (node (ref "X11") (pin "1") (pinfunction "1_1") (pintype "passive"))
      (node (ref "X24") (pin "P") (pinfunction "ANT_P") (pintype "bidirectional"))
    )
    (net (code "15") (name "IF_5") (class "Default")
      (node (ref "X12") (pin "1") (pinfunction "1_1") (pintype "passive"))
      (node (ref "X17") (pin "P") (pinfunction "ANT_P") (pintype "bidirectional"))
    )
    (net (code "16") (name "IF_6") (class "Default")
      (node (ref "X18") (pin "P") (pinfunction "ANT_P") (pintype "bidirectional"))
      (node (ref "X3") (pin "1") (pinfunction "1_1") (pintype "passive"))
    )
    (net (code "17") (name "IF_7") (class "Default")
      (node (ref "X19") (pin "P") (pinfunction "ANT_P") (pintype "bidirectional"))
      (node (ref "X4") (pin "1") (pinfunction "1_1") (pintype "passive"))
    )
    (net (code "18") (name "LCD_D4") (class "Default")
      (node (ref "JP2") (pin "13") (pinfunction "P$13_13") (pintype "bidirectional"))
      (node (ref "JP3") (pin "4") (pinfunction "4_4") (pintype "passive"))
    )
    (net (code "19") (name "LCD_D5") (class "Default")
      (node (ref "JP2") (pin "15") (pinfunction "P$15_15") (pintype "bidirectional"))
      (node (ref "JP3") (pin "5") (pinfunction "5_5") (pintype "passive"))
    )
    (net (code "20") (name "LCD_D6") (class "Default")
      (node (ref "JP2") (pin "12") (pinfunction "P$12_12") (pintype "bidirectional"))
      (node (ref "JP3") (pin "6") (pinfunction "6_6") (pintype "passive"))
    )
    (net (code "21") (name "LCD_D7") (class "Default")
      (node (ref "JP2") (pin "16") (pinfunction "GPIO.7_16") (pintype "bidirectional"))
      (node (ref "JP3") (pin "7") (pinfunction "7_7") (pintype "passive"))
    )
    (net (code "22") (name "LCD_EN") (class "Default")
      (node (ref "JP2") (pin "11") (pinfunction "P$11_11") (pintype "bidirectional"))
      (node (ref "JP3") (pin "3") (pinfunction "3_3") (pintype "passive"))
    )
    (net (code "23") (name "LCD_RS") (class "Default")
      (node (ref "JP2") (pin "7") (pinfunction "P$7_7") (pintype "bidirectional"))
      (node (ref "JP3") (pin "2") (pinfunction "2_2") (pintype "passive"))
    )
    (net (code "24") (name "LED1") (class "Default")
      (node (ref "JP2") (pin "35") (pinfunction "GPIO.0_35") (pintype "bidirectional"))
      (node (ref "JP5") (pin "1") (pinfunction "1_1") (pintype "passive"))
      (node (ref "R11") (pin "1") (pinfunction "1_1") (pintype "passive"))
    )
    (net (code "25") (name "LED2") (class "Default")
      (node (ref "JP2") (pin "36") (pinfunction "GPIO.1_36") (pintype "bidirectional"))
      (node (ref "JP5") (pin "2") (pinfunction "2_2") (pintype "passive"))
      (node (ref "R12") (pin "1") (pinfunction "1_1") (pintype "passive"))
    )
    (net (code "26") (name "LED3") (class "Default")
      (node (ref "JP2") (pin "32") (pinfunction "GPIO.2_32") (pintype "bidirectional"))
      (node (ref "JP5") (pin "3") (pinfunction "3_3") (pintype "passive"))
      (node (ref "R13") (pin "1") (pinfunction "1_1") (pintype "passive"))
    )
    (net (code "27") (name "LED4") (class "Default")
      (node (ref "JP2") (pin "31") (pinfunction "GPIO.3_31") (pintype "bidirectional"))
      (node (ref "JP5") (pin "4") (pinfunction "4_4") (pintype "passive"))
      (node (ref "R14") (pin "1") (pinfunction "1_1") (pintype "passive"))
    )
    (net (code "28") (name "LED5") (class "Default")
      (node (ref "JP2") (pin "29") (pinfunction "GPIO.4_29") (pintype "bidirectional"))
      (node (ref "JP5") (pin "5") (pinfunction "5_5") (pintype "passive"))
      (node (ref "R15") (pin "1") (pinfunction "1_1") (pintype "passive"))
    )
    (net (code "29") (name "LED6") (class "Default")
      (node (ref "JP2") (pin "18") (pinfunction "GPIO.5_18") (pintype "bidirectional"))
      (node (ref "JP5") (pin "6") (pinfunction "6_6") (pintype "passive"))
      (node (ref "R16") (pin "1") (pinfunction "1_1") (pintype "passive"))
    )
    (net (code "30") (name "LED7") (class "Default")
      (node (ref "JP2") (pin "22") (pinfunction "GPIO.6_22") (pintype "bidirectional"))
      (node (ref "JP5") (pin "7") (pinfunction "7_7") (pintype "passive"))
      (node (ref "R5") (pin "1") (pinfunction "1_1") (pintype "passive"))
    )
    (net (code "31") (name "LED8") (class "Default")
      (node (ref "JP2") (pin "23") (pinfunction "GPIO.8_23") (pintype "bidirectional"))
      (node (ref "JP5") (pin "9") (pinfunction "9_9") (pintype "passive"))
      (node (ref "R6") (pin "1") (pinfunction "1_1") (pintype "passive"))
    )
    (net (code "32") (name "LED9") (class "Default")
      (node (ref "JP2") (pin "21") (pinfunction "GPIO.9_21") (pintype "bidirectional"))
      (node (ref "JP5") (pin "10") (pinfunction "10_10") (pintype "passive"))
      (node (ref "R7") (pin "1") (pinfunction "1_1") (pintype "passive"))
    )
    (net (code "33") (name "LED10") (class "Default")
      (node (ref "JP2") (pin "19") (pinfunction "GPIO.10_19") (pintype "bidirectional"))
      (node (ref "JP5") (pin "11") (pinfunction "11_11") (pintype "passive"))
      (node (ref "R8") (pin "1") (pinfunction "1_1") (pintype "passive"))
    )
    (net (code "34") (name "LED11") (class "Default")
      (node (ref "JP2") (pin "33") (pinfunction "GPIO.11_33") (pintype "bidirectional"))
      (node (ref "JP5") (pin "12") (pinfunction "12_12") (pintype "passive"))
      (node (ref "R9") (pin "1") (pinfunction "1_1") (pintype "passive"))
    )
    (net (code "35") (name "MIXER_CLK") (class "Default")
      (node (ref "R32") (pin "1") (pinfunction "1_1") (pintype "passive"))
      (node (ref "X20") (pin "P") (pinfunction "ANT_P") (pintype "bidirectional"))
    )
    (net (code "36") (name "Net-(LED1-PadA)") (class "Default")
      (node (ref "LED1") (pin "A") (pinfunction "A_A") (pintype "passive"))
      (node (ref "R5") (pin "2") (pinfunction "2_2") (pintype "passive"))
    )
    (net (code "37") (name "Net-(LED2-PadA)") (class "Default")
      (node (ref "LED2") (pin "A") (pinfunction "A_A") (pintype "passive"))
      (node (ref "R6") (pin "2") (pinfunction "2_2") (pintype "passive"))
    )
    (net (code "38") (name "Net-(LED3-PadA)") (class "Default")
      (node (ref "LED3") (pin "A") (pinfunction "A_A") (pintype "passive"))
      (node (ref "R7") (pin "2") (pinfunction "2_2") (pintype "passive"))
    )
    (net (code "39") (name "Net-(LED4-PadA)") (class "Default")
      (node (ref "LED4") (pin "A") (pinfunction "A_A") (pintype "passive"))
      (node (ref "R8") (pin "2") (pinfunction "2_2") (pintype "passive"))
    )
    (net (code "40") (name "Net-(LED5-PadA)") (class "Default")
      (node (ref "LED5") (pin "A") (pinfunction "A_A") (pintype "passive"))
      (node (ref "R9") (pin "2") (pinfunction "2_2") (pintype "passive"))
    )
    (net (code "41") (name "Net-(LED6-PadA)") (class "Default")
      (node (ref "LED6") (pin "A") (pinfunction "A_A") (pintype "passive"))
      (node (ref "R11") (pin "2") (pinfunction "2_2") (pintype "passive"))
    )
    (net (code "42") (name "Net-(LED7-PadA)") (class "Default")
      (node (ref "LED7") (pin "A") (pinfunction "A_A") (pintype "passive"))
      (node (ref "R12") (pin "2") (pinfunction "2_2") (pintype "passive"))
    )
    (net (code "43") (name "Net-(LED8-PadA)") (class "Default")
      (node (ref "LED8") (pin "A") (pinfunction "A_A") (pintype "passive"))
      (node (ref "R13") (pin "2") (pinfunction "2_2") (pintype "passive"))
    )
    (net (code "44") (name "Net-(LED9-PadA)") (class "Default")
      (node (ref "LED9") (pin "A") (pinfunction "A_A") (pintype "passive"))
      (node (ref "R14") (pin "2") (pinfunction "2_2") (pintype "passive"))
    )
    (net (code "45") (name "Net-(LED10-PadA)") (class "Default")
      (node (ref "LED10") (pin "A") (pinfunction "A_A") (pintype "passive"))
      (node (ref "R15") (pin "2") (pinfunction "2_2") (pintype "passive"))
    )
    (net (code "46") (name "Net-(LED11-PadA)") (class "Default")
      (node (ref "LED11") (pin "A") (pinfunction "A_A") (pintype "passive"))
      (node (ref "R16") (pin "2") (pinfunction "2_2") (pintype "passive"))
    )
    (net (code "47") (name "Net-(PAD5-P)") (class "Default")
      (node (ref "F2") (pin "1") (pinfunction "1_1") (pintype "bidirectional"))
      (node (ref "PAD5") (pin "1") (pinfunction "P_1") (pintype "passive"))
    )
    (net (code "48") (name "Net-(PAD7-P)") (class "Default")
      (node (ref "F1") (pin "1") (pinfunction "1_1") (pintype "bidirectional"))
      (node (ref "PAD7") (pin "1") (pinfunction "P_1") (pintype "passive"))
    )
    (net (code "49") (name "Net-(PAD10-P)") (class "Default")
      (node (ref "PAD10") (pin "1") (pinfunction "P_1") (pintype "passive"))
      (node (ref "PAD9") (pin "1") (pinfunction "P_1") (pintype "passive"))
    )
    (net (code "50") (name "Net-(R1-Pad1)") (class "Default")
      (node (ref "R1") (pin "1") (pinfunction "1_1") (pintype "passive"))
      (node (ref "R2") (pin "E") (pinfunction "E_E") (pintype "passive"))
    )
    (net (code "51") (name "Net-(S1-P)") (class "Default")
      (node (ref "F1") (pin "2") (pinfunction "2_2") (pintype "bidirectional"))
      (node (ref "S1") (pin "2") (pinfunction "P_2") (pintype "passive"))
    )
    (net (code "52") (name "Net-(U3-EN)") (class "Default")
      (node (ref "C10") (pin "1") (pinfunction "1_1") (pintype "passive"))
      (node (ref "R10") (pin "1") (pinfunction "1_1") (pintype "passive"))
      (node (ref "U3") (pin "7") (pinfunction "VREF2_7") (pintype "power_in"))
      (node (ref "U3") (pin "8") (pinfunction "EN_8") (pintype "passive"))
    )
    (net (code "53") (name "Net-(U4-XIN{slash}CLK)") (class "Default")
      (node (ref "C11") (pin "2") (pinfunction "2_2") (pintype "passive"))
      (node (ref "R23") (pin "1") (pinfunction "1_1") (pintype "passive"))
      (node (ref "R24") (pin "2") (pinfunction "2_2") (pintype "passive"))
      (node (ref "U4") (pin "1") (pinfunction "XIN/CLK_1") (pintype "input"))
    )
    (net (code "54") (name "Net-(U4-XOUT)") (class "Default")
      (node (ref "C13") (pin "2") (pinfunction "2_2") (pintype "passive"))
      (node (ref "U4") (pin "24") (pinfunction "XOUT_24") (pintype "output"))
    )
    (net (code "55") (name "Net-(U4-Y1)") (class "Default")
      (node (ref "R25") (pin "2") (pinfunction "2_2") (pintype "passive"))
      (node (ref "U4") (pin "21") (pinfunction "Y1_21") (pintype "output"))
    )
    (net (code "56") (name "Net-(U4-Y2)") (class "Default")
      (node (ref "R26") (pin "2") (pinfunction "2_2") (pintype "passive"))
      (node (ref "U4") (pin "19") (pinfunction "Y2_19") (pintype "output"))
    )
    (net (code "57") (name "Net-(U4-Y3)") (class "Default")
      (node (ref "R27") (pin "2") (pinfunction "2_2") (pintype "passive"))
      (node (ref "U4") (pin "18") (pinfunction "Y3_18") (pintype "output"))
    )
    (net (code "58") (name "Net-(U4-Y4)") (class "Default")
      (node (ref "R28") (pin "2") (pinfunction "2_2") (pintype "passive"))
      (node (ref "U4") (pin "7") (pinfunction "Y4_7") (pintype "output"))
    )
    (net (code "59") (name "Net-(U4-Y5)") (class "Default")
      (node (ref "R29") (pin "2") (pinfunction "2_2") (pintype "passive"))
      (node (ref "U4") (pin "8") (pinfunction "Y5_8") (pintype "output"))
    )
    (net (code "60") (name "Net-(U4-Y6)") (class "Default")
      (node (ref "R30") (pin "2") (pinfunction "2_2") (pintype "passive"))
      (node (ref "U4") (pin "16") (pinfunction "Y6_16") (pintype "output"))
    )
    (net (code "61") (name "Net-(U4-Y7)") (class "Default")
      (node (ref "R31") (pin "2") (pinfunction "2_2") (pintype "passive"))
      (node (ref "U4") (pin "15") (pinfunction "Y7_15") (pintype "output"))
    )
    (net (code "62") (name "Net-(U4-Y8)") (class "Default")
      (node (ref "R32") (pin "2") (pinfunction "2_2") (pintype "passive"))
      (node (ref "U4") (pin "11") (pinfunction "Y8_11") (pintype "output"))
    )
    (net (code "63") (name "Net-(U4-Y9)") (class "Default")
      (node (ref "R33") (pin "2") (pinfunction "2_2") (pintype "passive"))
      (node (ref "U4") (pin "12") (pinfunction "Y9_12") (pintype "output"))
    )
    (net (code "64") (name "PLL_CLK9") (class "Default")
      (node (ref "R33") (pin "1") (pinfunction "1_1") (pintype "passive"))
      (node (ref "X9") (pin "P") (pinfunction "ANT_P") (pintype "bidirectional"))
    )
    (net (code "65") (name "PLL_CLKIN") (class "Default")
      (node (ref "C11") (pin "1") (pinfunction "1_1") (pintype "passive"))
      (node (ref "JP6") (pin "2") (pinfunction "2_2") (pintype "passive"))
    )
    (net (code "66") (name "PLL_SCL") (class "Default")
      (node (ref "R3") (pin "1") (pinfunction "1_1") (pintype "passive"))
      (node (ref "U3") (pin "3") (pinfunction "SCL1_3") (pintype "passive"))
      (node (ref "U4") (pin "22") (pinfunction "S2/SCL_22") (pintype "input"))
    )
    (net (code "67") (name "PLL_SDA") (class "Default")
      (node (ref "C9") (pin "1") (pinfunction "1_1") (pintype "passive"))
      (node (ref "R4") (pin "1") (pinfunction "1_1") (pintype "passive"))
      (node (ref "U3") (pin "4") (pinfunction "SDA1_4") (pintype "passive"))
      (node (ref "U4") (pin "23") (pinfunction "S1/SDA_23") (pintype "bidirectional"))
    )
    (net (code "68") (name "PLL_XOUT") (class "Default")
      (node (ref "C13") (pin "1") (pinfunction "1_1") (pintype "passive"))
      (node (ref "X25") (pin "P") (pinfunction "ANT_P") (pintype "bidirectional"))
    )
    (net (code "69") (name "S0") (class "Default")
      (node (ref "R21") (pin "1") (pinfunction "1_1") (pintype "passive"))
      (node (ref "R22") (pin "2") (pinfunction "2_2") (pintype "passive"))
      (node (ref "U4") (pin "2") (pinfunction "S0_2") (pintype "input"))
    )
    (net (code "70") (name "SCL1") (class "Default")
      (node (ref "JP2") (pin "5") (pinfunction "SCL1_5") (pintype "bidirectional"))
      (node (ref "R18") (pin "1") (pinfunction "1_1") (pintype "passive"))
      (node (ref "U3") (pin "6") (pinfunction "SCL2_6") (pintype "passive"))
    )
    (net (code "71") (name "SCL2") (class "Default")
      (node (ref "JP2") (pin "28") (pinfunction "SCL2_28") (pintype "bidirectional"))
      (node (ref "JP4") (pin "3") (pinfunction "3_3") (pintype "passive"))
    )
    (net (code "72") (name "SDA1") (class "Default")
      (node (ref "JP2") (pin "3") (pinfunction "SDA1_3") (pintype "bidirectional"))
      (node (ref "R17") (pin "1") (pinfunction "1_1") (pintype "passive"))
      (node (ref "U3") (pin "5") (pinfunction "SDA2_5") (pintype "passive"))
    )
    (net (code "73") (name "SDA2") (class "Default")
      (node (ref "JP2") (pin "27") (pinfunction "SDA2_27") (pintype "bidirectional"))
      (node (ref "JP4") (pin "2") (pinfunction "2_2") (pintype "passive"))
    )
    (net (code "74") (name "TXCO_10M") (class "Default")
      (node (ref "$3_194_$_2015-06-18_19-54-36") (pin "RF_OUT") (pinfunction "RF_OUT_RF_OUT") (pintype "bidirectional"))
      (node (ref "JP6") (pin "1") (pinfunction "1_1") (pintype "passive"))
    )
    (net (code "75") (name "VCC_5V") (class "Default")
      (node (ref "$3_194_$_2015-06-18_19-54-36") (pin "VCC") (pinfunction "VCC_VCC") (pintype "power_in"))
      (node (ref "C1") (pin "1") (pinfunction "1_1") (pintype "passive"))
      (node (ref "C2") (pin "1") (pinfunction "1_1") (pintype "passive"))
      (node (ref "C3") (pin "1") (pinfunction "1_1") (pintype "passive"))
      (node (ref "C4") (pin "1") (pinfunction "1_1") (pintype "passive"))
      (node (ref "C5") (pin "1") (pinfunction "1_1") (pintype "passive"))
      (node (ref "F2") (pin "2") (pinfunction "2_2") (pintype "bidirectional"))
      (node (ref "JP3") (pin "1") (pinfunction "1_1") (pintype "passive"))
      (node (ref "JP4") (pin "1") (pinfunction "1_1") (pintype "passive"))
      (node (ref "PAD1") (pin "1") (pinfunction "P_1") (pintype "passive"))
      (node (ref "PAD3") (pin "1") (pinfunction "P_1") (pintype "passive"))
      (node (ref "U1") (pin "3") (pinfunction "IN_2_3") (pintype "input"))
      (node (ref "U1") (pin "4") (pinfunction "IN_4") (pintype "input"))
      (node (ref "U2") (pin "3") (pinfunction "IN_2_3") (pintype "input"))
      (node (ref "U2") (pin "4") (pinfunction "IN_4") (pintype "input"))
    )
    (net (code "76") (name "VCC_12V") (class "Default")
      (node (ref "C14") (pin "1") (pinfunction "1_1") (pintype "passive"))
      (node (ref "C6") (pin "+") (pinfunction "+_+") (pintype "passive"))
      (node (ref "JP1") (pin "1") (pinfunction "1_1") (pintype "passive"))
      (node (ref "JP1") (pin "2") (pinfunction "2_2") (pintype "passive"))
      (node (ref "PAD8") (pin "1") (pinfunction "P_1") (pintype "passive"))
      (node (ref "S1") (pin "3") (pinfunction "S_3") (pintype "passive"))
    )
    (net (code "77") (name "VCTR") (class "Default")
      (node (ref "R19") (pin "1") (pinfunction "1_1") (pintype "passive"))
      (node (ref "R20") (pin "2") (pinfunction "2_2") (pintype "passive"))
      (node (ref "U4") (pin "4") (pinfunction "VCTR_4") (pintype "power_in"))
    )
    (net (code "78") (name "VDD_1.8V") (class "Default")
      (node (ref "C8") (pin "1") (pinfunction "1_1") (pintype "passive"))
      (node (ref "R1") (pin "2") (pinfunction "2_2") (pintype "passive"))
      (node (ref "R3") (pin "2") (pinfunction "2_2") (pintype "passive"))
      (node (ref "R4") (pin "2") (pinfunction "2_2") (pintype "passive"))
      (node (ref "U1") (pin "5") (pinfunction "OUT_2_5") (pintype "output"))
      (node (ref "U1") (pin "6") (pinfunction "OUT_6") (pintype "output"))
      (node (ref "U3") (pin "2") (pinfunction "VREF1_2") (pintype "power_in"))
      (node (ref "U4") (pin "13") (pinfunction "VDD_13") (pintype "power_in"))
      (node (ref "U4") (pin "3") (pinfunction "VDD_2_3") (pintype "power_in"))
    )
    (net (code "79") (name "VDD_3.3V") (class "Default")
      (node (ref "C12") (pin "1") (pinfunction "1_1") (pintype "passive"))
      (node (ref "C7") (pin "1") (pinfunction "1_1") (pintype "passive"))
      (node (ref "R10") (pin "2") (pinfunction "2_2") (pintype "passive"))
      (node (ref "R17") (pin "2") (pinfunction "2_2") (pintype "passive"))
      (node (ref "R18") (pin "2") (pinfunction "2_2") (pintype "passive"))
      (node (ref "R19") (pin "2") (pinfunction "2_2") (pintype "passive"))
      (node (ref "R21") (pin "2") (pinfunction "2_2") (pintype "passive"))
      (node (ref "R23") (pin "2") (pinfunction "2_2") (pintype "passive"))
      (node (ref "U2") (pin "5") (pinfunction "OUT_2_5") (pintype "output"))
      (node (ref "U2") (pin "6") (pinfunction "OUT_6") (pintype "output"))
      (node (ref "U4") (pin "10") (pinfunction "VDDOUT_3_10") (pintype "power_in"))
      (node (ref "U4") (pin "17") (pinfunction "VDDOUT_17") (pintype "power_in"))
      (node (ref "U4") (pin "6") (pinfunction "VDDOUT_2_6") (pintype "power_in"))
    )
    (net (code "80") (name "unconnected-(JP2-1V8-Pad38)") (class "Default")
      (node (ref "JP2") (pin "38") (pinfunction "1V8_38") (pintype "no_connect"))
    )
    (net (code "81") (name "unconnected-(JP2-3V3-Pad1)") (class "Default")
      (node (ref "JP2") (pin "1") (pinfunction "3V3_1") (pintype "no_connect"))
    )
    (net (code "82") (name "unconnected-(JP2-3V3-Pad17)") (class "Default")
      (node (ref "JP2") (pin "17") (pinfunction "3V3_17") (pintype "no_connect"))
    )
    (net (code "83") (name "unconnected-(JP2-5V-Pad2)") (class "Default")
      (node (ref "JP2") (pin "2") (pinfunction "5V_2") (pintype "no_connect"))
    )
    (net (code "84") (name "unconnected-(JP2-5V-Pad4)") (class "Default")
      (node (ref "JP2") (pin "4") (pinfunction "5V_4") (pintype "no_connect"))
    )
    (net (code "85") (name "unconnected-(JP2-ADC1-Pad37)") (class "Default")
      (node (ref "JP2") (pin "37") (pinfunction "ADC1_37") (pintype "bidirectional"))
    )
    (net (code "86") (name "unconnected-(JP2-P$24-Pad24)") (class "Default")
      (node (ref "JP2") (pin "24") (pinfunction "P$24_24") (pintype "bidirectional"))
    )
    (net (code "87") (name "unconnected-(JP2-P$26-Pad26)") (class "Default")
      (node (ref "JP2") (pin "26") (pinfunction "P$26_26") (pintype "bidirectional"))
    )
    (net (code "88") (name "unconnected-(JP2-RXD1-Pad10)") (class "Default")
      (node (ref "JP2") (pin "10") (pinfunction "RXD1_10") (pintype "bidirectional"))
    )
    (net (code "89") (name "unconnected-(JP2-TXD1-Pad8)") (class "Default")
      (node (ref "JP2") (pin "8") (pinfunction "TXD1_8") (pintype "bidirectional"))
    )
    (net (code "90") (name "unconnected-(JP5-Pad8)") (class "Default")
      (node (ref "JP5") (pin "8") (pinfunction "8_8") (pintype "passive"))
    )
    (net (code "91") (name "unconnected-(S1-O-Pad1)") (class "Default")
      (node (ref "S1") (pin "1") (pinfunction "O_1") (pintype "passive"))
    )
    (net (code "92") (name "unconnected-(U1-*RESET{slash}PG-Pad8)") (class "Default")
      (node (ref "U1") (pin "8") (pinfunction "*RESET/PG_8") (pintype "bidirectional"))
    )
    (net (code "93") (name "unconnected-(U1-FB{slash}NC-Pad7)") (class "Default")
      (node (ref "U1") (pin "7") (pinfunction "FB/NC_7") (pintype "bidirectional"))
    )
    (net (code "94") (name "unconnected-(U2-*RESET{slash}PG-Pad8)") (class "Default")
      (node (ref "U2") (pin "8") (pinfunction "*RESET/PG_8") (pintype "bidirectional"))
    )
    (net (code "95") (name "unconnected-(U2-FB{slash}NC-Pad7)") (class "Default")
      (node (ref "U2") (pin "7") (pinfunction "FB/NC_7") (pintype "bidirectional"))
    )
  )
)
